# mhyh.net
KiCad netlist of a schematic drawn in EAGLE
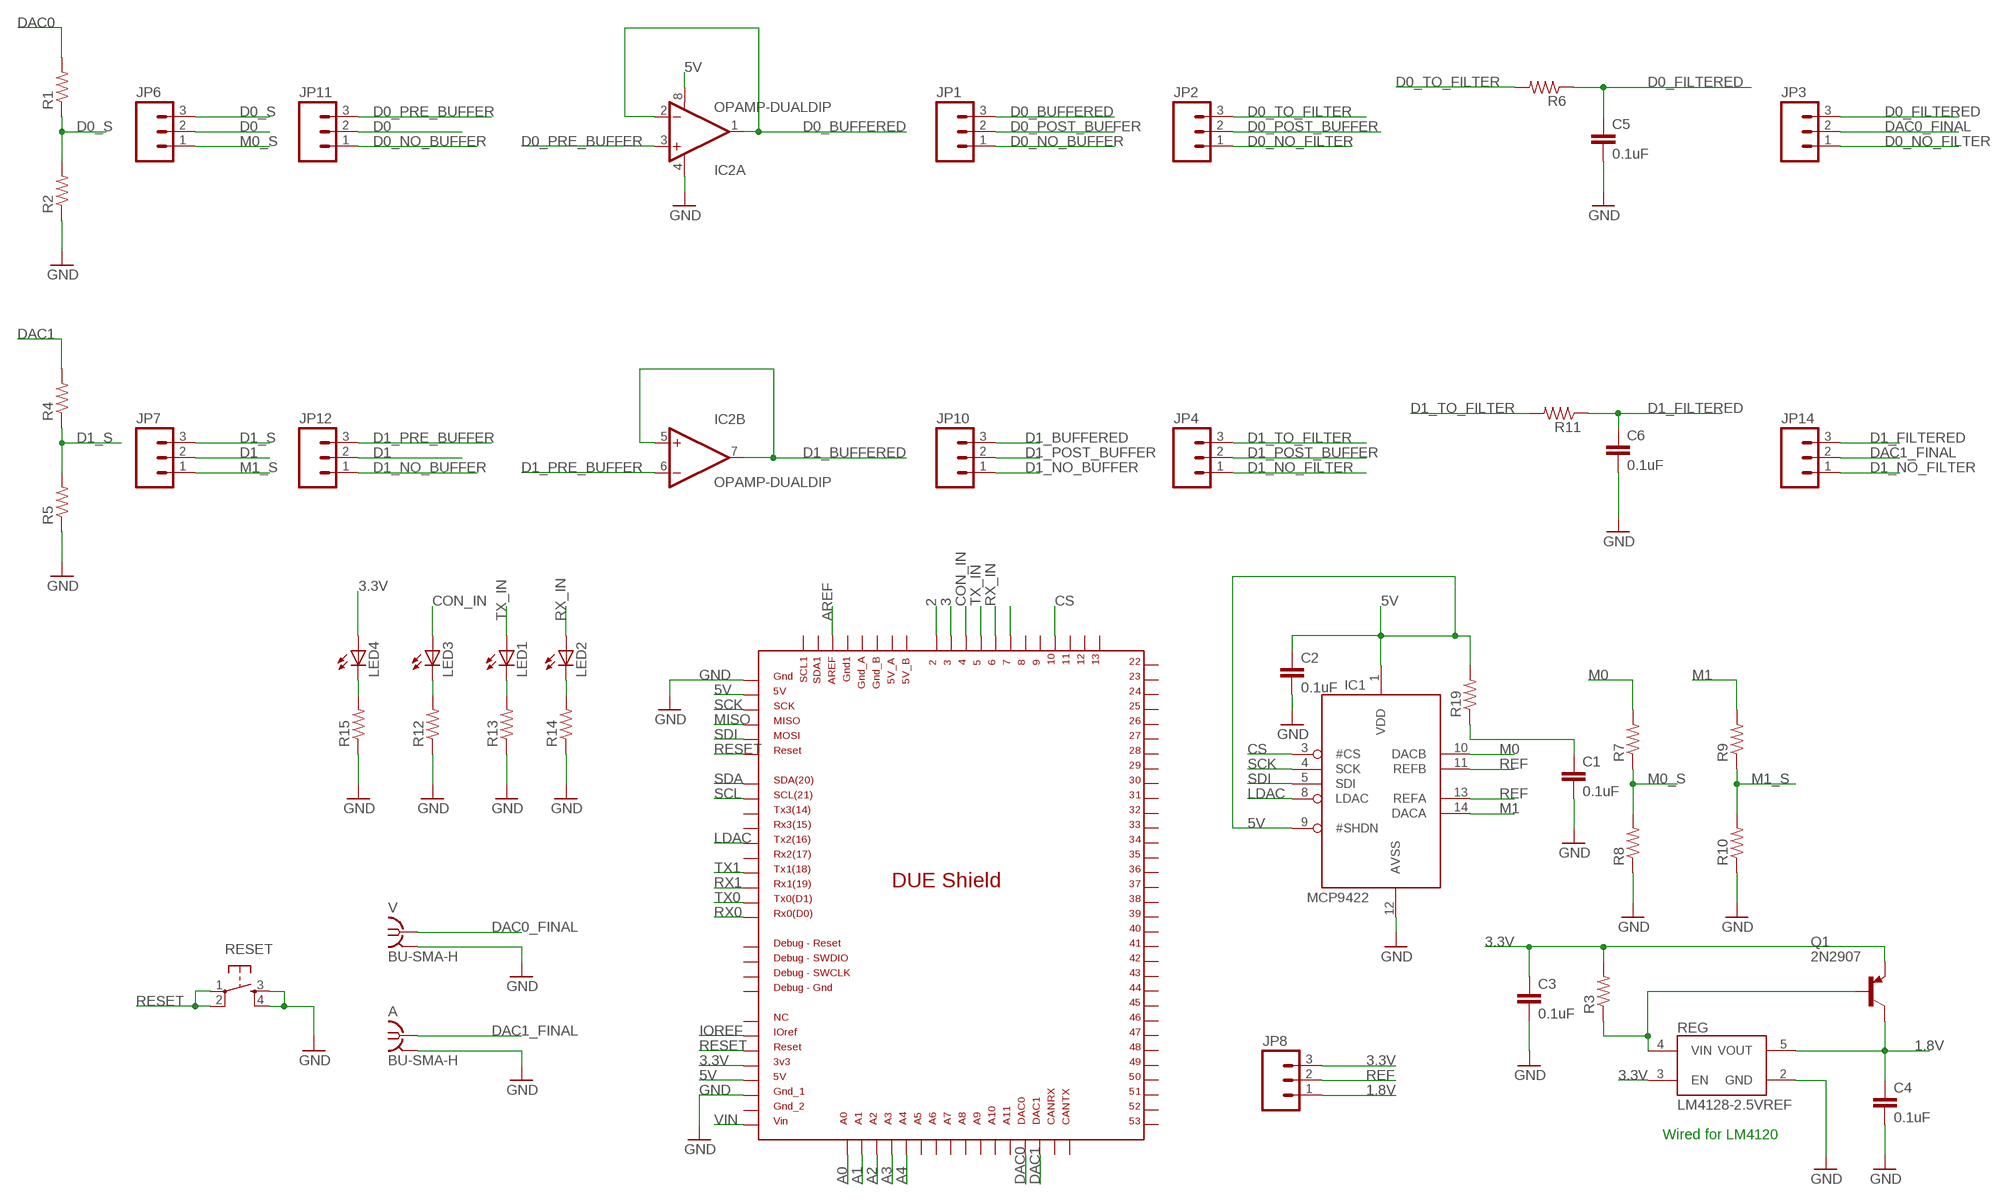
[diagram p0: schematic, sheet 1]

(export (version "E")
  (design (tool "Eeschema 10.0.6"))
  (components
    (comp (ref "A")
      (value "BU-SMA-H")
      (footprint "eagle-import:BU-SMA-H")
      (libsource (lib "eagle-import") (part "BU-SMA-H"))
    )
    (comp (ref "C1")
      (value "0.1uF")
      (footprint "eagle-import:0603-CAP")
      (libsource (lib "eagle-import") (part "0.1UF-25V-5%(0603)"))
    )
    (comp (ref "C2")
      (value "0.1uF")
      (footprint "eagle-import:0603-CAP")
      (libsource (lib "eagle-import") (part "0.1UF-25V-5%(0603)"))
    )
    (comp (ref "C3")
      (value "0.1uF")
      (footprint "eagle-import:0603-CAP")
      (libsource (lib "eagle-import") (part "0.1UF-25V-5%(0603)"))
    )
    (comp (ref "C4")
      (value "0.1uF")
      (footprint "eagle-import:0603-CAP")
      (libsource (lib "eagle-import") (part "0.1UF-25V-5%(0603)"))
    )
    (comp (ref "C5")
      (value "0.1uF")
      (footprint "eagle-import:0603-CAP")
      (libsource (lib "eagle-import") (part "0.1UF-25V-5%(0603)"))
    )
    (comp (ref "C6")
      (value "0.1uF")
      (footprint "eagle-import:0603-CAP")
      (libsource (lib "eagle-import") (part "0.1UF-25V-5%(0603)"))
    )
    (comp (ref "IC1")
      (value "MCP9422")
      (footprint "eagle-import:DIL14")
      (libsource (lib "eagle-import") (part "MCP9422"))
    )
    (comp (ref "IC2")
      (value "OPAMP-DUALDIP")
      (footprint "eagle-import:DIP08")
      (libsource (lib "eagle-import") (part "OPAMP-DUALDIP"))
    )
    (comp (ref "JP1")
      (value "M03LOCK")
      (footprint "eagle-import:1X03_LOCK")
      (libsource (lib "eagle-import") (part "M03LOCK"))
    )
    (comp (ref "JP2")
      (value "M03LOCK")
      (footprint "eagle-import:1X03_LOCK")
      (libsource (lib "eagle-import") (part "M03LOCK"))
    )
    (comp (ref "JP3")
      (value "M03LOCK")
      (footprint "eagle-import:1X03_LOCK")
      (libsource (lib "eagle-import") (part "M03LOCK"))
    )
    (comp (ref "JP4")
      (value "M03LOCK")
      (footprint "eagle-import:1X03_LOCK")
      (libsource (lib "eagle-import") (part "M03LOCK"))
    )
    (comp (ref "JP6")
      (value "M03LOCK")
      (footprint "eagle-import:1X03_LOCK")
      (libsource (lib "eagle-import") (part "M03LOCK"))
    )
    (comp (ref "JP7")
      (value "M03LOCK")
      (footprint "eagle-import:1X03_LOCK")
      (libsource (lib "eagle-import") (part "M03LOCK"))
    )
    (comp (ref "JP8")
      (value "M03LOCK")
      (footprint "eagle-import:1X03_LOCK")
      (libsource (lib "eagle-import") (part "M03LOCK"))
    )
    (comp (ref "JP10")
      (value "M03LOCK")
      (footprint "eagle-import:1X03_LOCK")
      (libsource (lib "eagle-import") (part "M03LOCK"))
    )
    (comp (ref "JP11")
      (value "M03LOCK")
      (footprint "eagle-import:1X03_LOCK")
      (libsource (lib "eagle-import") (part "M03LOCK"))
    )
    (comp (ref "JP12")
      (value "M03LOCK")
      (footprint "eagle-import:1X03_LOCK")
      (libsource (lib "eagle-import") (part "M03LOCK"))
    )
    (comp (ref "JP14")
      (value "M03LOCK")
      (footprint "eagle-import:1X03_LOCK")
      (libsource (lib "eagle-import") (part "M03LOCK"))
    )
    (comp (ref "LED1")
      (value "LEDCHIPLED_0603")
      (footprint "eagle-import:CHIPLED_0603")
      (libsource (lib "eagle-import") (part "LEDCHIPLED_0603"))
    )
    (comp (ref "LED2")
      (value "LEDCHIPLED_0603")
      (footprint "eagle-import:CHIPLED_0603")
      (libsource (lib "eagle-import") (part "LEDCHIPLED_0603"))
    )
    (comp (ref "LED3")
      (value "LEDCHIPLED_0603")
      (footprint "eagle-import:CHIPLED_0603")
      (libsource (lib "eagle-import") (part "LEDCHIPLED_0603"))
    )
    (comp (ref "LED4")
      (value "LEDCHIPLED_0603")
      (footprint "eagle-import:CHIPLED_0603")
      (libsource (lib "eagle-import") (part "LEDCHIPLED_0603"))
    )
    (comp (ref "Q1")
      (value "2N2907")
      (footprint "eagle-import:TO92-EBC-OVAL")
      (libsource (lib "eagle-import") (part "2N2907"))
    )
    (comp (ref "R1")
      (value "RESISTOR0603-RES")
      (footprint "eagle-import:0603-RES")
      (libsource (lib "eagle-import") (part "RESISTOR0603-RES"))
    )
    (comp (ref "R2")
      (value "RESISTOR0603-RES")
      (footprint "eagle-import:0603-RES")
      (libsource (lib "eagle-import") (part "RESISTOR0603-RES"))
    )
    (comp (ref "R3")
      (value "RESISTOR0603-RES")
      (footprint "eagle-import:0603-RES")
      (libsource (lib "eagle-import") (part "RESISTOR0603-RES"))
    )
    (comp (ref "R4")
      (value "RESISTOR0603-RES")
      (footprint "eagle-import:0603-RES")
      (libsource (lib "eagle-import") (part "RESISTOR0603-RES"))
    )
    (comp (ref "R5")
      (value "RESISTOR0603-RES")
      (footprint "eagle-import:0603-RES")
      (libsource (lib "eagle-import") (part "RESISTOR0603-RES"))
    )
    (comp (ref "R6")
      (value "RESISTOR0603-RES")
      (footprint "eagle-import:0603-RES")
      (libsource (lib "eagle-import") (part "RESISTOR0603-RES"))
    )
    (comp (ref "R7")
      (value "RESISTOR0603-RES")
      (footprint "eagle-import:0603-RES")
      (libsource (lib "eagle-import") (part "RESISTOR0603-RES"))
    )
    (comp (ref "R8")
      (value "RESISTOR0603-RES")
      (footprint "eagle-import:0603-RES")
      (libsource (lib "eagle-import") (part "RESISTOR0603-RES"))
    )
    (comp (ref "R9")
      (value "RESISTOR0603-RES")
      (footprint "eagle-import:0603-RES")
      (libsource (lib "eagle-import") (part "RESISTOR0603-RES"))
    )
    (comp (ref "R10")
      (value "RESISTOR0603-RES")
      (footprint "eagle-import:0603-RES")
      (libsource (lib "eagle-import") (part "RESISTOR0603-RES"))
    )
    (comp (ref "R11")
      (value "RESISTOR0603-RES")
      (footprint "eagle-import:0603-RES")
      (libsource (lib "eagle-import") (part "RESISTOR0603-RES"))
    )
    (comp (ref "R12")
      (value "RESISTOR0603-RES")
      (footprint "eagle-import:0603-RES")
      (libsource (lib "eagle-import") (part "RESISTOR0603-RES"))
    )
    (comp (ref "R13")
      (value "RESISTOR0603-RES")
      (footprint "eagle-import:0603-RES")
      (libsource (lib "eagle-import") (part "RESISTOR0603-RES"))
    )
    (comp (ref "R14")
      (value "RESISTOR0603-RES")
      (footprint "eagle-import:0603-RES")
      (libsource (lib "eagle-import") (part "RESISTOR0603-RES"))
    )
    (comp (ref "R15")
      (value "RESISTOR0603-RES")
      (footprint "eagle-import:0603-RES")
      (libsource (lib "eagle-import") (part "RESISTOR0603-RES"))
    )
    (comp (ref "R19")
      (value "RESISTOR0603-RES")
      (footprint "eagle-import:0603-RES")
      (libsource (lib "eagle-import") (part "RESISTOR0603-RES"))
    )
    (comp (ref "REG")
      (value "LM4128-2.5VREF")
      (footprint "eagle-import:SOT23-5")
      (libsource (lib "eagle-import") (part "LM4128-2.5VREF"))
    )
    (comp (ref "RESET")
      (value "TAC_SWITCHPTH")
      (footprint "eagle-import:TACTILE-PTH")
      (libsource (lib "eagle-import") (part "TAC_SWITCHPTH"))
    )
    (comp (ref "U$1")
      (value "DUE(NORMAL)")
      (footprint "eagle-import:DUE(NORMAL)")
      (libsource (lib "eagle-import") (part "DUE(NORMAL)"))
    )
    (comp (ref "V")
      (value "BU-SMA-H")
      (footprint "eagle-import:BU-SMA-H")
      (libsource (lib "eagle-import") (part "BU-SMA-H"))
    )
  )
  (nets
    (net (code "1") (name "/1.8V") (class "Default")
      (node (ref "C4") (pin "1") (pinfunction "1_1") (pintype "passive"))
      (node (ref "JP8") (pin "1") (pinfunction "1_1") (pintype "passive"))
      (node (ref "Q1") (pin "C") (pinfunction "C_C") (pintype "passive"))
      (node (ref "REG") (pin "5") (pinfunction "VOUT_5") (pintype "bidirectional"))
    )
    (net (code "2") (name "/2") (class "Default")
      (node (ref "U$1") (pin "2") (pinfunction "2_2") (pintype "bidirectional"))
    )
    (net (code "3") (name "/3") (class "Default")
      (node (ref "U$1") (pin "3") (pinfunction "3_3") (pintype "bidirectional"))
    )
    (net (code "4") (name "/3.3V") (class "Default")
      (node (ref "C3") (pin "1") (pinfunction "1_1") (pintype "passive"))
      (node (ref "JP8") (pin "3") (pinfunction "3_3") (pintype "passive"))
      (node (ref "LED4") (pin "A") (pinfunction "A_A") (pintype "passive"))
      (node (ref "Q1") (pin "E") (pinfunction "E_E") (pintype "passive"))
      (node (ref "R3") (pin "2") (pinfunction "2_2") (pintype "passive"))
      (node (ref "REG") (pin "3") (pinfunction "EN_3") (pintype "bidirectional"))
      (node (ref "U$1") (pin "3V3") (pinfunction "3V3_3V3") (pintype "bidirectional"))
    )
    (net (code "5") (name "/5V") (class "Default")
      (node (ref "C2") (pin "1") (pinfunction "1_1") (pintype "passive"))
      (node (ref "IC1") (pin "1") (pinfunction "VDD_1") (pintype "power_in"))
      (node (ref "IC1") (pin "9") (pinfunction "#SHDN_9") (pintype "input"))
      (node (ref "IC2") (pin "8") (pinfunction "V+_8") (pintype "power_in"))
      (node (ref "R19") (pin "2") (pinfunction "2_2") (pintype "passive"))
      (node (ref "U$1") (pin "5V") (pinfunction "5V_5V") (pintype "bidirectional"))
      (node (ref "U$1") (pin "GND_ICSP") (pinfunction "GND_ICSP_GND_ICSP") (pintype "bidirectional"))
    )
    (net (code "6") (name "/A0") (class "Default")
      (node (ref "U$1") (pin "A0") (pinfunction "A0_A0") (pintype "bidirectional"))
    )
    (net (code "7") (name "/A1") (class "Default")
      (node (ref "U$1") (pin "A1") (pinfunction "A1_A1") (pintype "bidirectional"))
    )
    (net (code "8") (name "/A2") (class "Default")
      (node (ref "U$1") (pin "A2") (pinfunction "A2_A2") (pintype "bidirectional"))
    )
    (net (code "9") (name "/A3") (class "Default")
      (node (ref "U$1") (pin "A3") (pinfunction "A3_A3") (pintype "bidirectional"))
    )
    (net (code "10") (name "/A4") (class "Default")
      (node (ref "U$1") (pin "A4") (pinfunction "A4_A4") (pintype "bidirectional"))
    )
    (net (code "11") (name "/AREF") (class "Default")
      (node (ref "U$1") (pin "AREF") (pinfunction "AREF_AREF") (pintype "bidirectional"))
    )
    (net (code "12") (name "/CON_IN") (class "Default")
      (node (ref "LED3") (pin "A") (pinfunction "A_A") (pintype "passive"))
      (node (ref "U$1") (pin "4") (pinfunction "4_4") (pintype "bidirectional"))
    )
    (net (code "13") (name "/CS") (class "Default")
      (node (ref "IC1") (pin "3") (pinfunction "#CS_3") (pintype "input"))
      (node (ref "U$1") (pin "10") (pinfunction "10_10") (pintype "bidirectional"))
    )
    (net (code "14") (name "/D0") (class "Default")
      (node (ref "JP11") (pin "2") (pinfunction "2_2") (pintype "passive"))
      (node (ref "JP6") (pin "2") (pinfunction "2_2") (pintype "passive"))
    )
    (net (code "15") (name "/D0_BUFFERED") (class "Default")
      (node (ref "IC2") (pin "1") (pinfunction "OUT_1") (pintype "output"))
      (node (ref "IC2") (pin "2") (pinfunction "-IN_2") (pintype "input"))
      (node (ref "JP1") (pin "3") (pinfunction "3_3") (pintype "passive"))
    )
    (net (code "16") (name "/D0_FILTERED") (class "Default")
      (node (ref "C5") (pin "1") (pinfunction "1_1") (pintype "passive"))
      (node (ref "JP3") (pin "3") (pinfunction "3_3") (pintype "passive"))
      (node (ref "R6") (pin "1") (pinfunction "1_1") (pintype "passive"))
    )
    (net (code "17") (name "/D0_NO_BUFFER") (class "Default")
      (node (ref "JP1") (pin "1") (pinfunction "1_1") (pintype "passive"))
      (node (ref "JP11") (pin "1") (pinfunction "1_1") (pintype "passive"))
    )
    (net (code "18") (name "/D0_NO_FILTER") (class "Default")
      (node (ref "JP2") (pin "1") (pinfunction "1_1") (pintype "passive"))
      (node (ref "JP3") (pin "1") (pinfunction "1_1") (pintype "passive"))
    )
    (net (code "19") (name "/D0_POST_BUFFER") (class "Default")
      (node (ref "JP1") (pin "2") (pinfunction "2_2") (pintype "passive"))
      (node (ref "JP2") (pin "2") (pinfunction "2_2") (pintype "passive"))
    )
    (net (code "20") (name "/D0_PRE_BUFFER") (class "Default")
      (node (ref "IC2") (pin "3") (pinfunction "+IN_3") (pintype "input"))
      (node (ref "JP11") (pin "3") (pinfunction "3_3") (pintype "passive"))
    )
    (net (code "21") (name "/D0_S") (class "Default")
      (node (ref "JP6") (pin "3") (pinfunction "3_3") (pintype "passive"))
      (node (ref "R1") (pin "1") (pinfunction "1_1") (pintype "passive"))
      (node (ref "R2") (pin "2") (pinfunction "2_2") (pintype "passive"))
    )
    (net (code "22") (name "/D0_TO_FILTER") (class "Default")
      (node (ref "JP2") (pin "3") (pinfunction "3_3") (pintype "passive"))
      (node (ref "R6") (pin "2") (pinfunction "2_2") (pintype "passive"))
    )
    (net (code "23") (name "/D1") (class "Default")
      (node (ref "JP12") (pin "2") (pinfunction "2_2") (pintype "passive"))
      (node (ref "JP7") (pin "2") (pinfunction "2_2") (pintype "passive"))
    )
    (net (code "24") (name "/D1_BUFFERED") (class "Default")
      (node (ref "IC2") (pin "5") (pinfunction "+IN_5") (pintype "input"))
      (node (ref "IC2") (pin "7") (pinfunction "OUT_7") (pintype "output"))
      (node (ref "JP10") (pin "3") (pinfunction "3_3") (pintype "passive"))
    )
    (net (code "25") (name "/D1_FILTERED") (class "Default")
      (node (ref "C6") (pin "1") (pinfunction "1_1") (pintype "passive"))
      (node (ref "JP14") (pin "3") (pinfunction "3_3") (pintype "passive"))
      (node (ref "R11") (pin "1") (pinfunction "1_1") (pintype "passive"))
    )
    (net (code "26") (name "/D1_NO_BUFFER") (class "Default")
      (node (ref "JP10") (pin "1") (pinfunction "1_1") (pintype "passive"))
      (node (ref "JP12") (pin "1") (pinfunction "1_1") (pintype "passive"))
    )
    (net (code "27") (name "/D1_NO_FILTER") (class "Default")
      (node (ref "JP14") (pin "1") (pinfunction "1_1") (pintype "passive"))
      (node (ref "JP4") (pin "1") (pinfunction "1_1") (pintype "passive"))
    )
    (net (code "28") (name "/D1_POST_BUFFER") (class "Default")
      (node (ref "JP10") (pin "2") (pinfunction "2_2") (pintype "passive"))
      (node (ref "JP4") (pin "2") (pinfunction "2_2") (pintype "passive"))
    )
    (net (code "29") (name "/D1_PRE_BUFFER") (class "Default")
      (node (ref "IC2") (pin "6") (pinfunction "-IN_6") (pintype "input"))
      (node (ref "JP12") (pin "3") (pinfunction "3_3") (pintype "passive"))
    )
    (net (code "30") (name "/D1_S") (class "Default")
      (node (ref "JP7") (pin "3") (pinfunction "3_3") (pintype "passive"))
      (node (ref "R4") (pin "1") (pinfunction "1_1") (pintype "passive"))
      (node (ref "R5") (pin "2") (pinfunction "2_2") (pintype "passive"))
    )
    (net (code "31") (name "/D1_TO_FILTER") (class "Default")
      (node (ref "JP4") (pin "3") (pinfunction "3_3") (pintype "passive"))
      (node (ref "R11") (pin "2") (pinfunction "2_2") (pintype "passive"))
    )
    (net (code "32") (name "/DAC0") (class "Default")
      (node (ref "R1") (pin "2") (pinfunction "2_2") (pintype "passive"))
      (node (ref "U$1") (pin "DAC0") (pinfunction "DAC0_DAC0") (pintype "bidirectional"))
    )
    (net (code "33") (name "/DAC0_FINAL") (class "Default")
      (node (ref "JP3") (pin "2") (pinfunction "2_2") (pintype "passive"))
      (node (ref "V") (pin "1") (pinfunction "1_1") (pintype "passive"))
    )
    (net (code "34") (name "/DAC1") (class "Default")
      (node (ref "R4") (pin "2") (pinfunction "2_2") (pintype "passive"))
      (node (ref "U$1") (pin "DAC1") (pinfunction "DAC1_DAC1") (pintype "bidirectional"))
    )
    (net (code "35") (name "/DAC1_FINAL") (class "Default")
      (node (ref "A") (pin "1") (pinfunction "1_1") (pintype "passive"))
      (node (ref "JP14") (pin "2") (pinfunction "2_2") (pintype "passive"))
    )
    (net (code "36") (name "/IOREF") (class "Default")
      (node (ref "U$1") (pin "IOREF") (pinfunction "IOREF_IOREF") (pintype "bidirectional"))
    )
    (net (code "37") (name "/LDAC") (class "Default")
      (node (ref "IC1") (pin "8") (pinfunction "LDAC_8") (pintype "input"))
      (node (ref "U$1") (pin "TX2") (pinfunction "TX2_TX2") (pintype "bidirectional"))
    )
    (net (code "38") (name "/M0") (class "Default")
      (node (ref "IC1") (pin "10") (pinfunction "DACB_10") (pintype "output"))
      (node (ref "R7") (pin "2") (pinfunction "2_2") (pintype "passive"))
    )
    (net (code "39") (name "/M0_S") (class "Default")
      (node (ref "JP6") (pin "1") (pinfunction "1_1") (pintype "passive"))
      (node (ref "R7") (pin "1") (pinfunction "1_1") (pintype "passive"))
      (node (ref "R8") (pin "2") (pinfunction "2_2") (pintype "passive"))
    )
    (net (code "40") (name "/M1") (class "Default")
      (node (ref "IC1") (pin "14") (pinfunction "DACA_14") (pintype "output"))
      (node (ref "R9") (pin "2") (pinfunction "2_2") (pintype "passive"))
    )
    (net (code "41") (name "/M1_S") (class "Default")
      (node (ref "JP7") (pin "1") (pinfunction "1_1") (pintype "passive"))
      (node (ref "R10") (pin "2") (pinfunction "2_2") (pintype "passive"))
      (node (ref "R9") (pin "1") (pinfunction "1_1") (pintype "passive"))
    )
    (net (code "42") (name "/MISO") (class "Default")
      (node (ref "U$1") (pin "MISO_ICSP") (pinfunction "MISO_ICSP_MISO_ICSP") (pintype "bidirectional"))
    )
    (net (code "43") (name "/REF") (class "Default")
      (node (ref "IC1") (pin "11") (pinfunction "REFB_11") (pintype "input"))
      (node (ref "IC1") (pin "13") (pinfunction "REFA_13") (pintype "input"))
      (node (ref "JP8") (pin "2") (pinfunction "2_2") (pintype "passive"))
    )
    (net (code "44") (name "/RESET") (class "Default")
      (node (ref "RESET") (pin "1") (pinfunction "1_1") (pintype "passive"))
      (node (ref "RESET") (pin "2") (pinfunction "2_2") (pintype "passive"))
      (node (ref "U$1") (pin "RESET") (pinfunction "RESET_RESET") (pintype "bidirectional"))
      (node (ref "U$1") (pin "RESET_ICSP") (pinfunction "RESET_ICSP_RESET_ICSP") (pintype "bidirectional"))
    )
    (net (code "45") (name "/RX0") (class "Default")
      (node (ref "U$1") (pin "RX0") (pinfunction "RX0_RX0") (pintype "bidirectional"))
    )
    (net (code "46") (name "/RX1") (class "Default")
      (node (ref "U$1") (pin "RX1") (pinfunction "RX1_RX1") (pintype "bidirectional"))
    )
    (net (code "47") (name "/RX_IN") (class "Default")
      (node (ref "LED2") (pin "A") (pinfunction "A_A") (pintype "passive"))
      (node (ref "U$1") (pin "6") (pinfunction "6_6") (pintype "bidirectional"))
    )
    (net (code "48") (name "/SCK") (class "Default")
      (node (ref "IC1") (pin "4") (pinfunction "SCK_4") (pintype "input"))
      (node (ref "U$1") (pin "SCK_ICSP") (pinfunction "SCK_ICSP_SCK_ICSP") (pintype "bidirectional"))
    )
    (net (code "49") (name "/SCL") (class "Default")
      (node (ref "U$1") (pin "SCL") (pinfunction "SCL_SCL") (pintype "bidirectional"))
    )
    (net (code "50") (name "/SDA") (class "Default")
      (node (ref "U$1") (pin "SDA") (pinfunction "SDA_SDA") (pintype "bidirectional"))
    )
    (net (code "51") (name "/SDI") (class "Default")
      (node (ref "IC1") (pin "5") (pinfunction "SDI_5") (pintype "input"))
      (node (ref "U$1") (pin "MOSI_ICSP") (pinfunction "MOSI_ICSP_MOSI_ICSP") (pintype "bidirectional"))
    )
    (net (code "52") (name "/TX0") (class "Default")
      (node (ref "U$1") (pin "TX0") (pinfunction "TX0_TX0") (pintype "bidirectional"))
    )
    (net (code "53") (name "/TX1") (class "Default")
      (node (ref "U$1") (pin "TX1") (pinfunction "TX1_TX1") (pintype "bidirectional"))
    )
    (net (code "54") (name "/TX_IN") (class "Default")
      (node (ref "LED1") (pin "A") (pinfunction "A_A") (pintype "passive"))
      (node (ref "U$1") (pin "5") (pinfunction "5_5") (pintype "bidirectional"))
    )
    (net (code "55") (name "/VIN") (class "Default")
      (node (ref "U$1") (pin "VIN") (pinfunction "VIN_VIN") (pintype "bidirectional"))
    )
    (net (code "56") (name "GND") (class "Default")
      (node (ref "A") (pin "2") (pinfunction "2_2") (pintype "passive"))
      (node (ref "A") (pin "3") (pinfunction "2_3") (pintype "passive"))
      (node (ref "A") (pin "4") (pinfunction "2_4") (pintype "passive"))
      (node (ref "A") (pin "5") (pinfunction "2_5") (pintype "passive"))
      (node (ref "C1") (pin "2") (pinfunction "2_2") (pintype "passive"))
      (node (ref "C2") (pin "2") (pinfunction "2_2") (pintype "passive"))
      (node (ref "C3") (pin "2") (pinfunction "2_2") (pintype "passive"))
      (node (ref "C4") (pin "2") (pinfunction "2_2") (pintype "passive"))
      (node (ref "C5") (pin "2") (pinfunction "2_2") (pintype "passive"))
      (node (ref "C6") (pin "2") (pinfunction "2_2") (pintype "passive"))
      (node (ref "IC1") (pin "12") (pinfunction "AVSS_12") (pintype "power_in"))
      (node (ref "IC2") (pin "4") (pinfunction "V-_4") (pintype "power_in"))
      (node (ref "R10") (pin "1") (pinfunction "1_1") (pintype "passive"))
      (node (ref "R12") (pin "1") (pinfunction "1_1") (pintype "passive"))
      (node (ref "R13") (pin "1") (pinfunction "1_1") (pintype "passive"))
      (node (ref "R14") (pin "1") (pinfunction "1_1") (pintype "passive"))
      (node (ref "R15") (pin "1") (pinfunction "1_1") (pintype "passive"))
      (node (ref "R2") (pin "1") (pinfunction "1_1") (pintype "passive"))
      (node (ref "R5") (pin "1") (pinfunction "1_1") (pintype "passive"))
      (node (ref "R8") (pin "1") (pinfunction "1_1") (pintype "passive"))
      (node (ref "REG") (pin "2") (pinfunction "GND_2") (pintype "bidirectional"))
      (node (ref "RESET") (pin "3") (pinfunction "3_3") (pintype "passive"))
      (node (ref "RESET") (pin "4") (pinfunction "4_4") (pintype "passive"))
      (node (ref "U$1") (pin "5V_ICSP") (pinfunction "5V_ICSP_5V_ICSP") (pintype "bidirectional"))
      (node (ref "U$1") (pin "GND_1") (pinfunction "GND_1_GND_1") (pintype "bidirectional"))
      (node (ref "V") (pin "2") (pinfunction "2_2") (pintype "passive"))
      (node (ref "V") (pin "3") (pinfunction "2_3") (pintype "passive"))
      (node (ref "V") (pin "4") (pinfunction "2_4") (pintype "passive"))
      (node (ref "V") (pin "5") (pinfunction "2_5") (pintype "passive"))
    )
    (net (code "57") (name "Net-(C1-Pad1)") (class "Default")
      (node (ref "C1") (pin "1") (pinfunction "1_1") (pintype "passive"))
      (node (ref "R19") (pin "1") (pinfunction "1_1") (pintype "passive"))
    )
    (net (code "58") (name "Net-(LED1-PadC)") (class "Default")
      (node (ref "LED1") (pin "C") (pinfunction "C_C") (pintype "passive"))
      (node (ref "R13") (pin "2") (pinfunction "2_2") (pintype "passive"))
    )
    (net (code "59") (name "Net-(LED2-PadC)") (class "Default")
      (node (ref "LED2") (pin "C") (pinfunction "C_C") (pintype "passive"))
      (node (ref "R14") (pin "2") (pinfunction "2_2") (pintype "passive"))
    )
    (net (code "60") (name "Net-(LED3-PadC)") (class "Default")
      (node (ref "LED3") (pin "C") (pinfunction "C_C") (pintype "passive"))
      (node (ref "R12") (pin "2") (pinfunction "2_2") (pintype "passive"))
    )
    (net (code "61") (name "Net-(LED4-PadC)") (class "Default")
      (node (ref "LED4") (pin "C") (pinfunction "C_C") (pintype "passive"))
      (node (ref "R15") (pin "2") (pinfunction "2_2") (pintype "passive"))
    )
    (net (code "62") (name "Net-(REG-VIN)") (class "Default")
      (node (ref "Q1") (pin "B") (pinfunction "B_B") (pintype "passive"))
      (node (ref "R3") (pin "1") (pinfunction "1_1") (pintype "passive"))
      (node (ref "REG") (pin "4") (pinfunction "VIN_4") (pintype "bidirectional"))
    )
    (net (code "63") (name "unconnected-(U$1-Pad5V_A)") (class "Default")
      (node (ref "U$1") (pin "5V_A") (pinfunction "5V_A_5V_A") (pintype "bidirectional"))
    )
    (net (code "64") (name "unconnected-(U$1-Pad5V_B)") (class "Default")
      (node (ref "U$1") (pin "5V_B") (pinfunction "5V_B_5V_B") (pintype "bidirectional"))
    )
    (net (code "65") (name "unconnected-(U$1-Pad7)") (class "Default")
      (node (ref "U$1") (pin "7") (pinfunction "7_7") (pintype "bidirectional"))
    )
    (net (code "66") (name "unconnected-(U$1-Pad8)") (class "Default")
      (node (ref "U$1") (pin "8") (pinfunction "8_8") (pintype "bidirectional"))
    )
    (net (code "67") (name "unconnected-(U$1-Pad9)") (class "Default")
      (node (ref "U$1") (pin "9") (pinfunction "9_9") (pintype "bidirectional"))
    )
    (net (code "68") (name "unconnected-(U$1-Pad11)") (class "Default")
      (node (ref "U$1") (pin "11") (pinfunction "11_11") (pintype "bidirectional"))
    )
    (net (code "69") (name "unconnected-(U$1-Pad12)") (class "Default")
      (node (ref "U$1") (pin "12") (pinfunction "12_12") (pintype "bidirectional"))
    )
    (net (code "70") (name "unconnected-(U$1-Pad13)") (class "Default")
      (node (ref "U$1") (pin "13") (pinfunction "13_13") (pintype "bidirectional"))
    )
    (net (code "71") (name "unconnected-(U$1-Pad22)") (class "Default")
      (node (ref "U$1") (pin "22") (pinfunction "22_22") (pintype "bidirectional"))
    )
    (net (code "72") (name "unconnected-(U$1-Pad23)") (class "Default")
      (node (ref "U$1") (pin "23") (pinfunction "23_23") (pintype "bidirectional"))
    )
    (net (code "73") (name "unconnected-(U$1-Pad24)") (class "Default")
      (node (ref "U$1") (pin "24") (pinfunction "24_24") (pintype "bidirectional"))
    )
    (net (code "74") (name "unconnected-(U$1-Pad25)") (class "Default")
      (node (ref "U$1") (pin "25") (pinfunction "25_25") (pintype "bidirectional"))
    )
    (net (code "75") (name "unconnected-(U$1-Pad26)") (class "Default")
      (node (ref "U$1") (pin "26") (pinfunction "26_26") (pintype "bidirectional"))
    )
    (net (code "76") (name "unconnected-(U$1-Pad27)") (class "Default")
      (node (ref "U$1") (pin "27") (pinfunction "27_27") (pintype "bidirectional"))
    )
    (net (code "77") (name "unconnected-(U$1-Pad28)") (class "Default")
      (node (ref "U$1") (pin "28") (pinfunction "28_28") (pintype "bidirectional"))
    )
    (net (code "78") (name "unconnected-(U$1-Pad29)") (class "Default")
      (node (ref "U$1") (pin "29") (pinfunction "29_29") (pintype "bidirectional"))
    )
    (net (code "79") (name "unconnected-(U$1-Pad30)") (class "Default")
      (node (ref "U$1") (pin "30") (pinfunction "30_30") (pintype "bidirectional"))
    )
    (net (code "80") (name "unconnected-(U$1-Pad31)") (class "Default")
      (node (ref "U$1") (pin "31") (pinfunction "31_31") (pintype "bidirectional"))
    )
    (net (code "81") (name "unconnected-(U$1-Pad32)") (class "Default")
      (node (ref "U$1") (pin "32") (pinfunction "32_32") (pintype "bidirectional"))
    )
    (net (code "82") (name "unconnected-(U$1-Pad33)") (class "Default")
      (node (ref "U$1") (pin "33") (pinfunction "33_33") (pintype "bidirectional"))
    )
    (net (code "83") (name "unconnected-(U$1-Pad34)") (class "Default")
      (node (ref "U$1") (pin "34") (pinfunction "34_34") (pintype "bidirectional"))
    )
    (net (code "84") (name "unconnected-(U$1-Pad35)") (class "Default")
      (node (ref "U$1") (pin "35") (pinfunction "35_35") (pintype "bidirectional"))
    )
    (net (code "85") (name "unconnected-(U$1-Pad36)") (class "Default")
      (node (ref "U$1") (pin "36") (pinfunction "36_36") (pintype "bidirectional"))
    )
    (net (code "86") (name "unconnected-(U$1-Pad37)") (class "Default")
      (node (ref "U$1") (pin "37") (pinfunction "37_37") (pintype "bidirectional"))
    )
    (net (code "87") (name "unconnected-(U$1-Pad38)") (class "Default")
      (node (ref "U$1") (pin "38") (pinfunction "38_38") (pintype "bidirectional"))
    )
    (net (code "88") (name "unconnected-(U$1-Pad39)") (class "Default")
      (node (ref "U$1") (pin "39") (pinfunction "39_39") (pintype "bidirectional"))
    )
    (net (code "89") (name "unconnected-(U$1-Pad40)") (class "Default")
      (node (ref "U$1") (pin "40") (pinfunction "40_40") (pintype "bidirectional"))
    )
    (net (code "90") (name "unconnected-(U$1-Pad41)") (class "Default")
      (node (ref "U$1") (pin "41") (pinfunction "41_41") (pintype "bidirectional"))
    )
    (net (code "91") (name "unconnected-(U$1-Pad42)") (class "Default")
      (node (ref "U$1") (pin "42") (pinfunction "42_42") (pintype "bidirectional"))
    )
    (net (code "92") (name "unconnected-(U$1-Pad43)") (class "Default")
      (node (ref "U$1") (pin "43") (pinfunction "43_43") (pintype "bidirectional"))
    )
    (net (code "93") (name "unconnected-(U$1-Pad44)") (class "Default")
      (node (ref "U$1") (pin "44") (pinfunction "44_44") (pintype "bidirectional"))
    )
    (net (code "94") (name "unconnected-(U$1-Pad45)") (class "Default")
      (node (ref "U$1") (pin "45") (pinfunction "45_45") (pintype "bidirectional"))
    )
    (net (code "95") (name "unconnected-(U$1-Pad46)") (class "Default")
      (node (ref "U$1") (pin "46") (pinfunction "46_46") (pintype "bidirectional"))
    )
    (net (code "96") (name "unconnected-(U$1-Pad47)") (class "Default")
      (node (ref "U$1") (pin "47") (pinfunction "47_47") (pintype "bidirectional"))
    )
    (net (code "97") (name "unconnected-(U$1-Pad48)") (class "Default")
      (node (ref "U$1") (pin "48") (pinfunction "48_48") (pintype "bidirectional"))
    )
    (net (code "98") (name "unconnected-(U$1-Pad49)") (class "Default")
      (node (ref "U$1") (pin "49") (pinfunction "49_49") (pintype "bidirectional"))
    )
    (net (code "99") (name "unconnected-(U$1-Pad50)") (class "Default")
      (node (ref "U$1") (pin "50") (pinfunction "50_50") (pintype "bidirectional"))
    )
    (net (code "100") (name "unconnected-(U$1-Pad51)") (class "Default")
      (node (ref "U$1") (pin "51") (pinfunction "51_51") (pintype "bidirectional"))
    )
    (net (code "101") (name "unconnected-(U$1-Pad52)") (class "Default")
      (node (ref "U$1") (pin "52") (pinfunction "52_52") (pintype "bidirectional"))
    )
    (net (code "102") (name "unconnected-(U$1-Pad53)") (class "Default")
      (node (ref "U$1") (pin "53") (pinfunction "53_53") (pintype "bidirectional"))
    )
    (net (code "103") (name "unconnected-(U$1-PadA5)") (class "Default")
      (node (ref "U$1") (pin "A5") (pinfunction "A5_A5") (pintype "bidirectional"))
    )
    (net (code "104") (name "unconnected-(U$1-PadA6)") (class "Default")
      (node (ref "U$1") (pin "A6") (pinfunction "A6_A6") (pintype "bidirectional"))
    )
    (net (code "105") (name "unconnected-(U$1-PadA7)") (class "Default")
      (node (ref "U$1") (pin "A7") (pinfunction "A7_A7") (pintype "bidirectional"))
    )
    (net (code "106") (name "unconnected-(U$1-PadA8)") (class "Default")
      (node (ref "U$1") (pin "A8") (pinfunction "A8_A8") (pintype "bidirectional"))
    )
    (net (code "107") (name "unconnected-(U$1-PadA9)") (class "Default")
      (node (ref "U$1") (pin "A9") (pinfunction "A9_A9") (pintype "bidirectional"))
    )
    (net (code "108") (name "unconnected-(U$1-PadA10)") (class "Default")
      (node (ref "U$1") (pin "A10") (pinfunction "A10_A10") (pintype "bidirectional"))
    )
    (net (code "109") (name "unconnected-(U$1-PadA11)") (class "Default")
      (node (ref "U$1") (pin "A11") (pinfunction "A11_A11") (pintype "bidirectional"))
    )
    (net (code "110") (name "unconnected-(U$1-PadCANRX)") (class "Default")
      (node (ref "U$1") (pin "CANRX") (pinfunction "CANRX_CANRX") (pintype "bidirectional"))
    )
    (net (code "111") (name "unconnected-(U$1-PadCANTX)") (class "Default")
      (node (ref "U$1") (pin "CANTX") (pinfunction "CANTX_CANTX") (pintype "bidirectional"))
    )
    (net (code "112") (name "unconnected-(U$1-PadGND1)") (class "Default")
      (node (ref "U$1") (pin "GND1") (pinfunction "GND1_GND1") (pintype "bidirectional"))
    )
    (net (code "113") (name "unconnected-(U$1-PadGND_2)") (class "Default")
      (node (ref "U$1") (pin "GND_2") (pinfunction "GND_2_GND_2") (pintype "bidirectional"))
    )
    (net (code "114") (name "unconnected-(U$1-PadGND_A)") (class "Default")
      (node (ref "U$1") (pin "GND_A") (pinfunction "GND_A_GND_A") (pintype "bidirectional"))
    )
    (net (code "115") (name "unconnected-(U$1-PadGND_B)") (class "Default")
      (node (ref "U$1") (pin "GND_B") (pinfunction "GND_B_GND_B") (pintype "bidirectional"))
    )
    (net (code "116") (name "unconnected-(U$1-PadGND_DEBUG)") (class "Default")
      (node (ref "U$1") (pin "GND_DEBUG") (pinfunction "GND_DEBUG_GND_DEBUG") (pintype "bidirectional"))
    )
    (net (code "117") (name "unconnected-(U$1-PadNC)") (class "Default")
      (node (ref "U$1") (pin "NC") (pinfunction "NC_NC") (pintype "bidirectional"))
    )
    (net (code "118") (name "unconnected-(U$1-PadRESET_DEBUG)") (class "Default")
      (node (ref "U$1") (pin "RESET_DEBUG") (pinfunction "RESET_DEBUG_RESET_DEBUG") (pintype "bidirectional"))
    )
    (net (code "119") (name "unconnected-(U$1-PadRX2)") (class "Default")
      (node (ref "U$1") (pin "RX2") (pinfunction "RX2_RX2") (pintype "bidirectional"))
    )
    (net (code "120") (name "unconnected-(U$1-PadRX3)") (class "Default")
      (node (ref "U$1") (pin "RX3") (pinfunction "RX3_RX3") (pintype "bidirectional"))
    )
    (net (code "121") (name "unconnected-(U$1-PadSCL1)") (class "Default")
      (node (ref "U$1") (pin "SCL1") (pinfunction "SCL1_SCL1") (pintype "bidirectional"))
    )
    (net (code "122") (name "unconnected-(U$1-PadSDA1)") (class "Default")
      (node (ref "U$1") (pin "SDA1") (pinfunction "SDA1_SDA1") (pintype "bidirectional"))
    )
    (net (code "123") (name "unconnected-(U$1-PadSWCLK_DEBUG)") (class "Default")
      (node (ref "U$1") (pin "SWCLK_DEBUG") (pinfunction "SWCLK_DEBUG_SWCLK_DEBUG") (pintype "bidirectional"))
    )
    (net (code "124") (name "unconnected-(U$1-PadSWDIO_DEBUG)") (class "Default")
      (node (ref "U$1") (pin "SWDIO_DEBUG") (pinfunction "SWDIO_DEBUG_SWDIO_DEBUG") (pintype "bidirectional"))
    )
    (net (code "125") (name "unconnected-(U$1-PadTX3)") (class "Default")
      (node (ref "U$1") (pin "TX3") (pinfunction "TX3_TX3") (pintype "bidirectional"))
    )
  )
)
